# Power_Regulators.net
KiCad netlist of a schematic drawn in Altium Designer
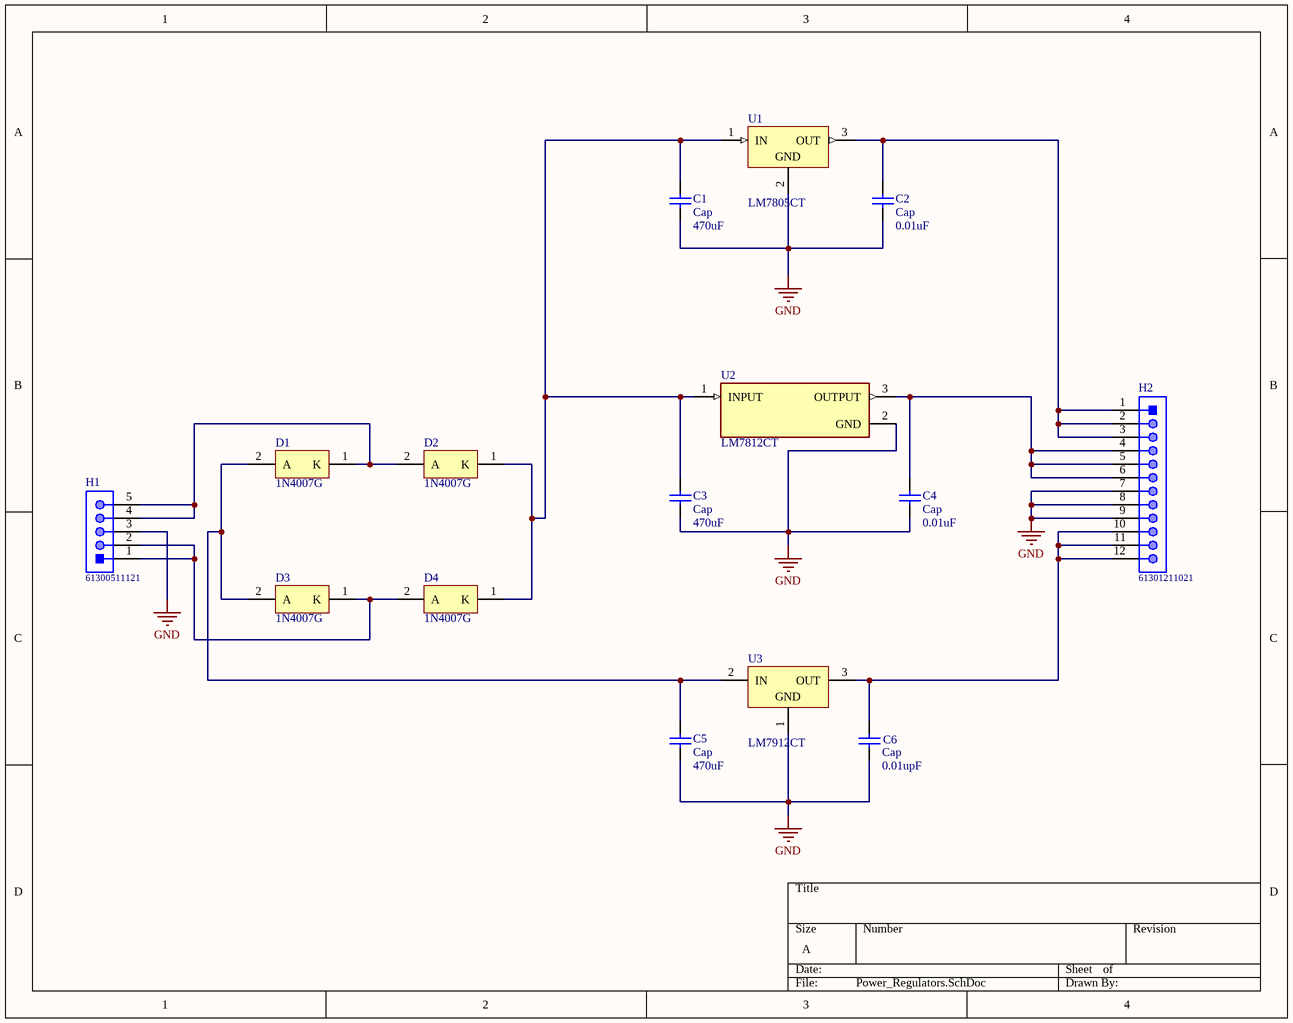
[diagram p0: Power_Regulators.SchDoc]

(export (version "E")
  (design (tool "Eeschema 10.0.6"))
  (components
    (comp (ref "C1")
      (value "Cap")
      (footprint "RAD-0.3")
      (description "Capacitor")
      (fields (field (name "ALTIUM_VALUE") "470uF") (field (name "PUBLISHER") "Altium Limited"))
      (libsource (lib "Miscellaneous Devices") (part "Cap"))
    )
    (comp (ref "C2")
      (value "Cap")
      (footprint "RAD-0.3")
      (description "Capacitor")
      (fields (field (name "ALTIUM_VALUE") "0.01uF") (field (name "PUBLISHER") "Altium Limited"))
      (libsource (lib "Miscellaneous Devices") (part "Cap"))
    )
    (comp (ref "C3")
      (value "Cap")
      (footprint "RAD-0.3")
      (description "Capacitor")
      (fields (field (name "ALTIUM_VALUE") "470uF") (field (name "PUBLISHER") "Altium Limited"))
      (libsource (lib "Miscellaneous Devices") (part "Cap"))
    )
    (comp (ref "C4")
      (value "Cap")
      (footprint "RAD-0.3")
      (description "Capacitor")
      (fields (field (name "ALTIUM_VALUE") "0.01uF") (field (name "PUBLISHER") "Altium Limited"))
      (libsource (lib "Miscellaneous Devices") (part "Cap"))
    )
    (comp (ref "C5")
      (value "Cap")
      (footprint "RAD-0.3")
      (description "Capacitor")
      (fields (field (name "ALTIUM_VALUE") "470uF") (field (name "PUBLISHER") "Altium Limited"))
      (libsource (lib "Miscellaneous Devices") (part "Cap"))
    )
    (comp (ref "C6")
      (value "Cap")
      (footprint "RAD-0.3")
      (description "Capacitor")
      (fields (field (name "ALTIUM_VALUE") "0.01upF") (field (name "PUBLISHER") "Altium Limited"))
      (libsource (lib "Miscellaneous Devices") (part "Cap"))
    )
    (comp (ref "D1")
      (value "1N4007G")
      (footprint "ONSC-AXIAL_LEAD-2-59-10_P")
      (description "Standard Recovery Rectifier, 2-Pin Axial_Lead, Pb-Free, Bulk Bag")
      (fields (field (name "MANUFACTURER") "On Semiconductor"))
      (libsource (lib "Altium Content Vault") (part "ONSC-D-K1A2-2_A"))
    )
    (comp (ref "D2")
      (value "1N4007G")
      (footprint "ONSC-AXIAL_LEAD-2-59-10_P")
      (description "Standard Recovery Rectifier, 2-Pin Axial_Lead, Pb-Free, Bulk Bag")
      (fields (field (name "MANUFACTURER") "On Semiconductor"))
      (libsource (lib "Altium Content Vault") (part "ONSC-D-K1A2-2_A"))
    )
    (comp (ref "D3")
      (value "1N4007G")
      (footprint "ONSC-AXIAL_LEAD-2-59-10_P")
      (description "Standard Recovery Rectifier, 2-Pin Axial_Lead, Pb-Free, Bulk Bag")
      (fields (field (name "MANUFACTURER") "On Semiconductor"))
      (libsource (lib "Altium Content Vault") (part "ONSC-D-K1A2-2_A"))
    )
    (comp (ref "D4")
      (value "1N4007G")
      (footprint "ONSC-AXIAL_LEAD-2-59-10_P")
      (description "Standard Recovery Rectifier, 2-Pin Axial_Lead, Pb-Free, Bulk Bag")
      (fields (field (name "MANUFACTURER") "On Semiconductor"))
      (libsource (lib "Altium Content Vault") (part "ONSC-D-K1A2-2_A"))
    )
    (comp (ref "H1")
      (value "61300511121")
      (footprint "61300511121")
      (description "THT Vertical Pin Header WR-PHD, Pitch 2.54 mm, Single Row, 5 pins")
      (fields (field (name "MANUFACTURER") "Wurth Elektronik") (field (name "PUBLISHER") "WurthElektronik"))
      (libsource (lib "Altium Content Vault") (part "WE-CN-1P-M-R5"))
    )
    (comp (ref "H2")
      (value "61301211021")
      (footprint "61301211021")
      (description "THT Angled Pin Header WR-PHD, Pitch 2.54 mm, Single Row, 12 pins")
      (fields (field (name "MANUFACTURER") "Wurth Elektronik") (field (name "PUBLISHER") "WurthElektronik"))
      (libsource (lib "Altium Content Vault") (part "WE-CN-1P-M-R12"))
    )
    (comp (ref "U1")
      (value "LM7805CT")
      (footprint "FAIR-TO-220-3")
      (description "Positive Voltage Regulator, 5 V, 1 A, -40 to 125 degC, 3-Pin TO-220, RoHS, Tube")
      (fields (field (name "MANUFACTURER") "FairchildSemiconductor"))
      (libsource (lib "Altium Content Vault") (part "FAIR-LM7805CT-TO220-3"))
    )
    (comp (ref "U2")
      (value "LM7812CT")
      (footprint "FP-TO220B03-MFG")
      (description "IC REG LINEAR 12V 1A TO220-3")
      (fields
        (field (name "OCTOPART") "https://octopart.com/lm7812ct-on+semiconductor-14383031")
        (field (name "OBSOLETE PART") "true")
      )
      (libsource (lib "Altium Content Vault") (part "6207a8f1a6b4db326a9e0a8a99b4969"))
    )
    (comp (ref "U3")
      (value "LM7912CT")
      (footprint "NDE0003A")
      (description "3-Terminal Negative Regulator, 3-pin TO-220")
      (fields (field (name "MANUFACTURER") "Texas Instruments"))
      (libsource (lib "Altium Content Vault") (part "PM-REG-LM7905-SIL3"))
    )
  )
  (nets
    (net (code "1") (name "GND") (class "Default")
      (node (ref "C1") (pin "1") (pinfunction "1_1") (pintype "passive"))
      (node (ref "C2") (pin "1") (pinfunction "1_1") (pintype "passive"))
      (node (ref "C3") (pin "1") (pinfunction "1_1") (pintype "passive"))
      (node (ref "C4") (pin "1") (pinfunction "1_1") (pintype "passive"))
      (node (ref "C5") (pin "1") (pinfunction "1_1") (pintype "passive"))
      (node (ref "C6") (pin "1") (pinfunction "1_1") (pintype "passive"))
      (node (ref "H1") (pin "3") (pinfunction "3_3") (pintype "passive"))
      (node (ref "H2") (pin "7") (pinfunction "7_7") (pintype "passive"))
      (node (ref "H2") (pin "8") (pinfunction "8_8") (pintype "passive"))
      (node (ref "H2") (pin "9") (pinfunction "9_9") (pintype "passive"))
      (node (ref "U1") (pin "2") (pinfunction "GND_2") (pintype "power_in"))
      (node (ref "U2") (pin "2") (pinfunction "GND_2") (pintype "power_in"))
      (node (ref "U3") (pin "1") (pinfunction "GND_1") (pintype "power_in"))
    )
    (net (code "2") (name "Net-(D1-A)") (class "Default")
      (node (ref "C5") (pin "2") (pinfunction "2_2") (pintype "passive"))
      (node (ref "D1") (pin "2") (pinfunction "A_2") (pintype "passive"))
      (node (ref "D3") (pin "2") (pinfunction "A_2") (pintype "passive"))
      (node (ref "U3") (pin "2") (pinfunction "IN_2") (pintype "power_in"))
    )
    (net (code "3") (name "Net-(D1-K)") (class "Default")
      (node (ref "D1") (pin "1") (pinfunction "K_1") (pintype "passive"))
      (node (ref "D2") (pin "2") (pinfunction "A_2") (pintype "passive"))
      (node (ref "H1") (pin "4") (pinfunction "4_4") (pintype "passive"))
      (node (ref "H1") (pin "5") (pinfunction "5_5") (pintype "passive"))
    )
    (net (code "4") (name "Net-(D2-K)") (class "Default")
      (node (ref "C1") (pin "2") (pinfunction "2_2") (pintype "passive"))
      (node (ref "C3") (pin "2") (pinfunction "2_2") (pintype "passive"))
      (node (ref "D2") (pin "1") (pinfunction "K_1") (pintype "passive"))
      (node (ref "D4") (pin "1") (pinfunction "K_1") (pintype "passive"))
      (node (ref "U1") (pin "1") (pinfunction "IN_1") (pintype "input"))
      (node (ref "U2") (pin "1") (pinfunction "INPUT_1") (pintype "input"))
    )
    (net (code "5") (name "Net-(D3-K)") (class "Default")
      (node (ref "D3") (pin "1") (pinfunction "K_1") (pintype "passive"))
      (node (ref "D4") (pin "2") (pinfunction "A_2") (pintype "passive"))
      (node (ref "H1") (pin "1") (pinfunction "1_1") (pintype "passive"))
      (node (ref "H1") (pin "2") (pinfunction "2_2") (pintype "passive"))
    )
    (net (code "6") (name "Net-(U1-OUT)") (class "Default")
      (node (ref "C2") (pin "2") (pinfunction "2_2") (pintype "passive"))
      (node (ref "H2") (pin "1") (pinfunction "1_1") (pintype "passive"))
      (node (ref "H2") (pin "2") (pinfunction "2_2") (pintype "passive"))
      (node (ref "H2") (pin "3") (pinfunction "3_3") (pintype "passive"))
      (node (ref "U1") (pin "3") (pinfunction "OUT_3") (pintype "output"))
    )
    (net (code "7") (name "Net-(U2-OUTPUT)") (class "Default")
      (node (ref "C4") (pin "2") (pinfunction "2_2") (pintype "passive"))
      (node (ref "H2") (pin "4") (pinfunction "4_4") (pintype "passive"))
      (node (ref "H2") (pin "5") (pinfunction "5_5") (pintype "passive"))
      (node (ref "H2") (pin "6") (pinfunction "6_6") (pintype "passive"))
      (node (ref "U2") (pin "3") (pinfunction "OUTPUT_3") (pintype "output"))
    )
    (net (code "8") (name "Net-(U3-OUT)") (class "Default")
      (node (ref "C6") (pin "2") (pinfunction "2_2") (pintype "passive"))
      (node (ref "H2") (pin "10") (pinfunction "10_10") (pintype "passive"))
      (node (ref "H2") (pin "11") (pinfunction "11_11") (pintype "passive"))
      (node (ref "H2") (pin "12") (pinfunction "12_12") (pintype "passive"))
      (node (ref "U3") (pin "3") (pinfunction "OUT_3") (pintype "power_in"))
    )
  )
)
